# MA_board_1.net
KiCad netlist of a schematic drawn in EAGLE
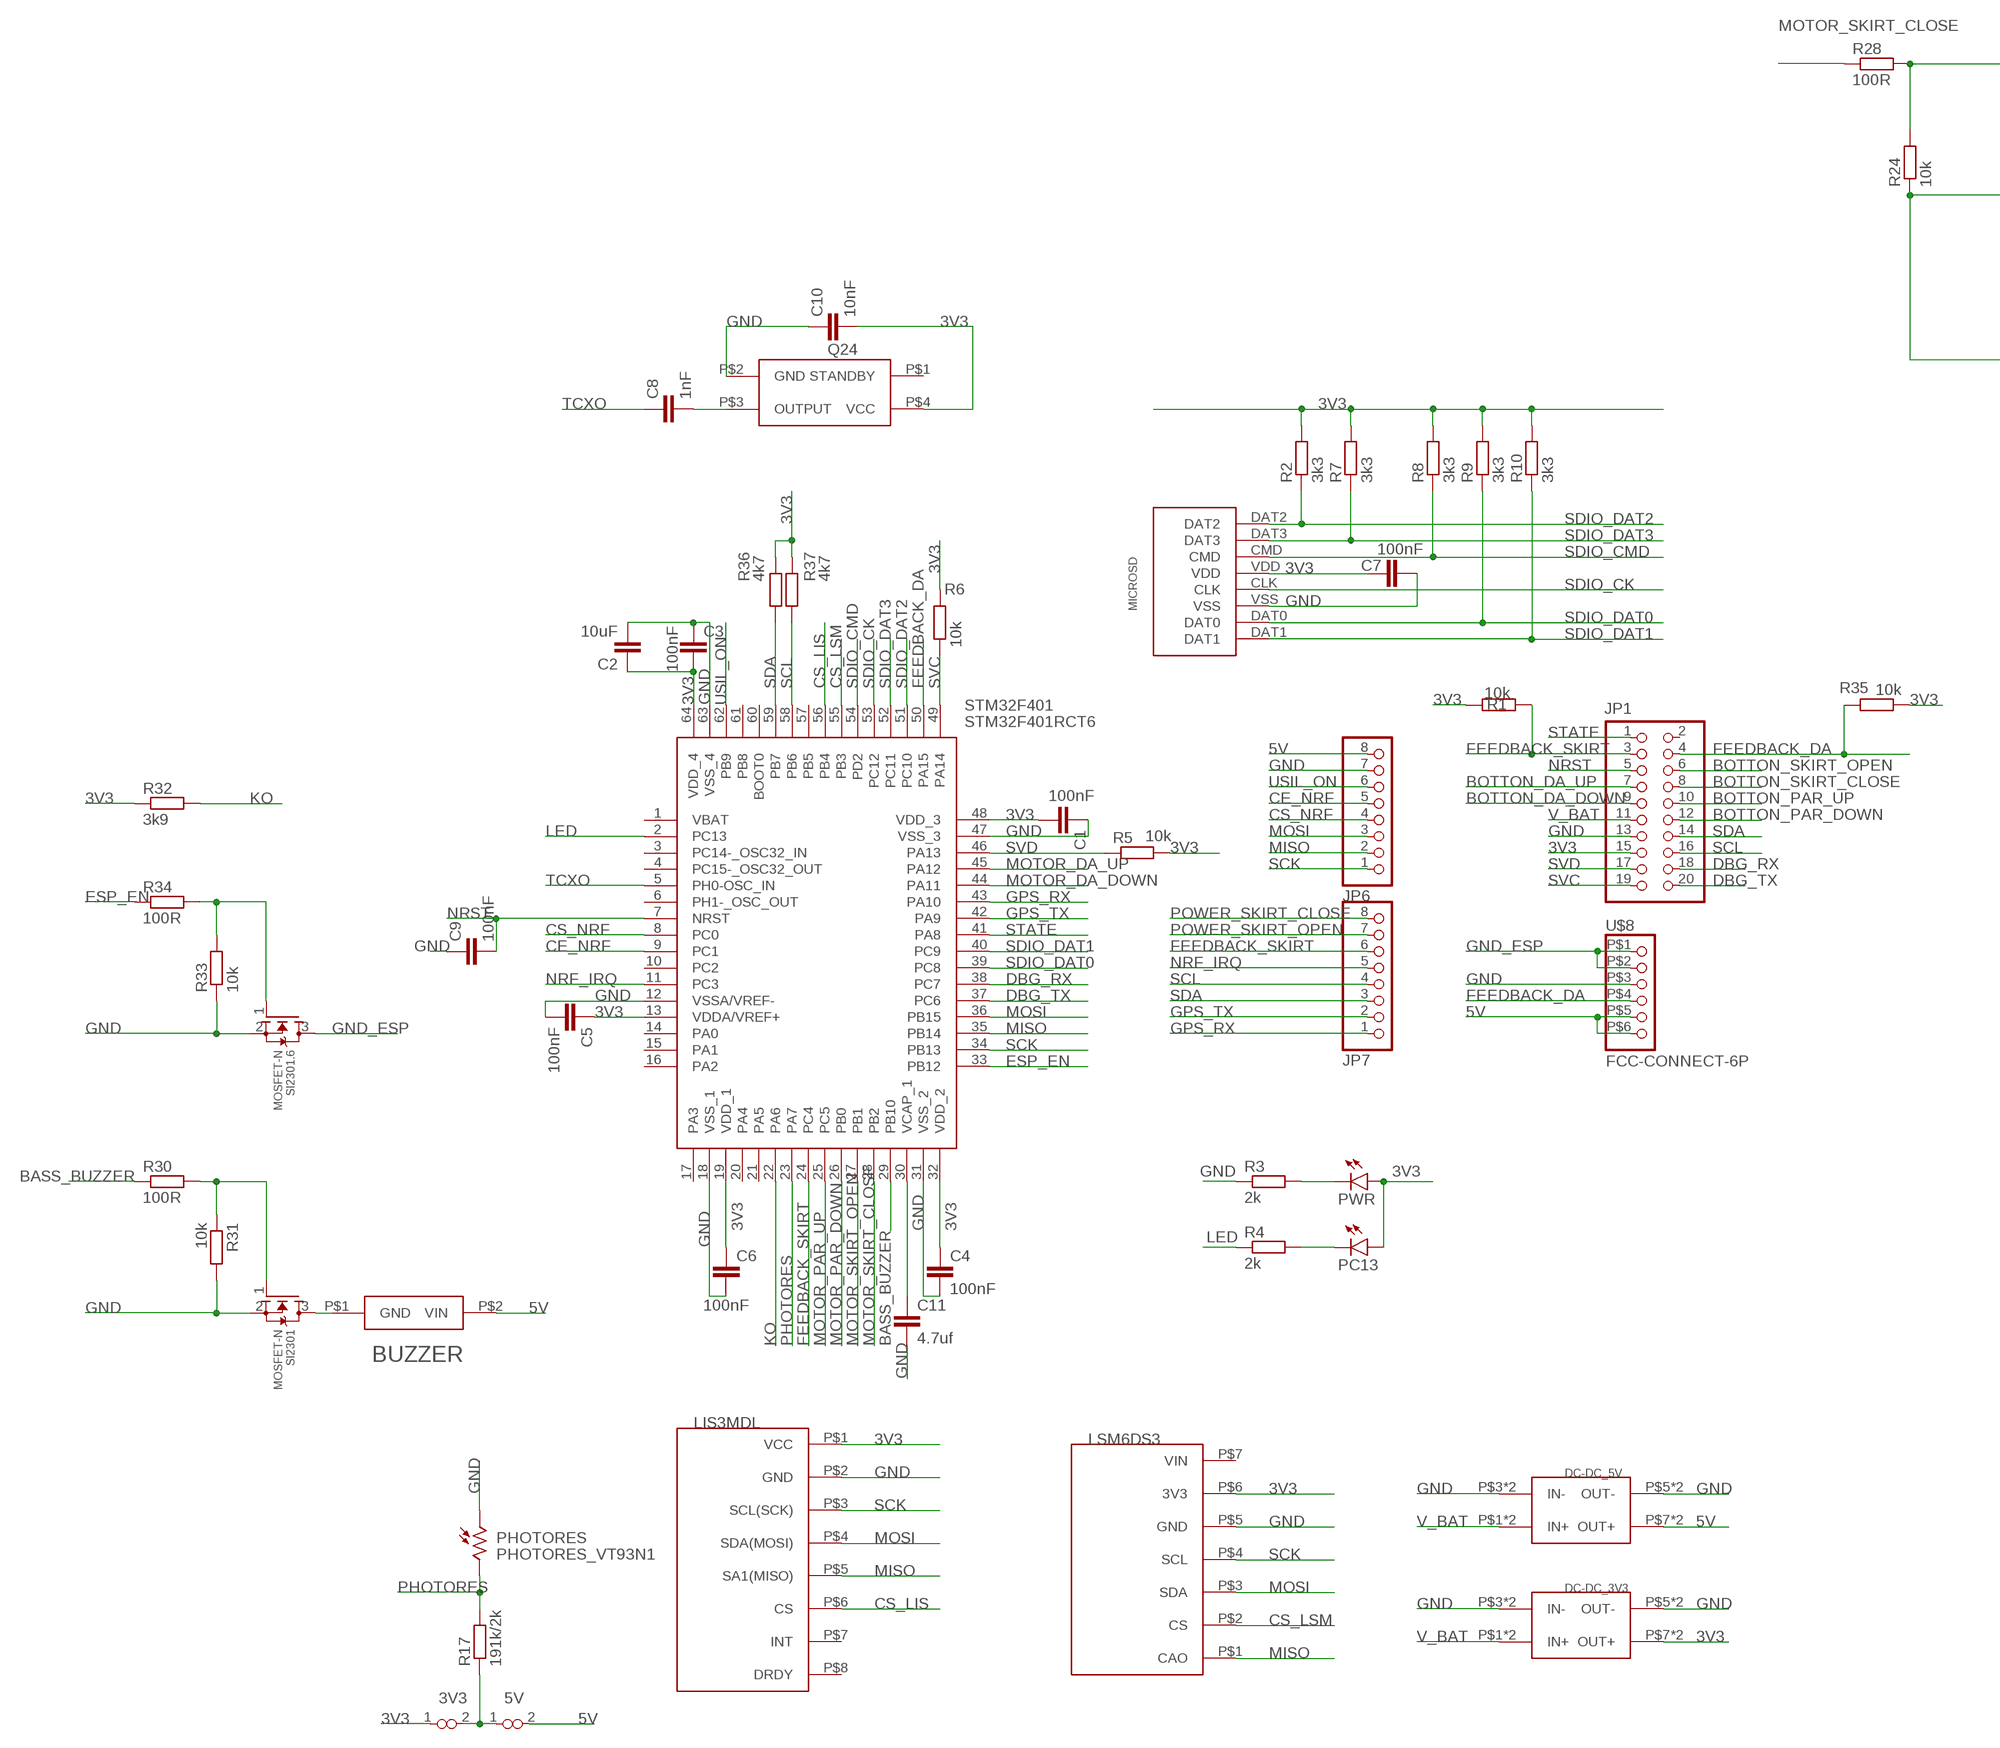
[diagram p0: schematic, sheet 1, part 1 of 2]
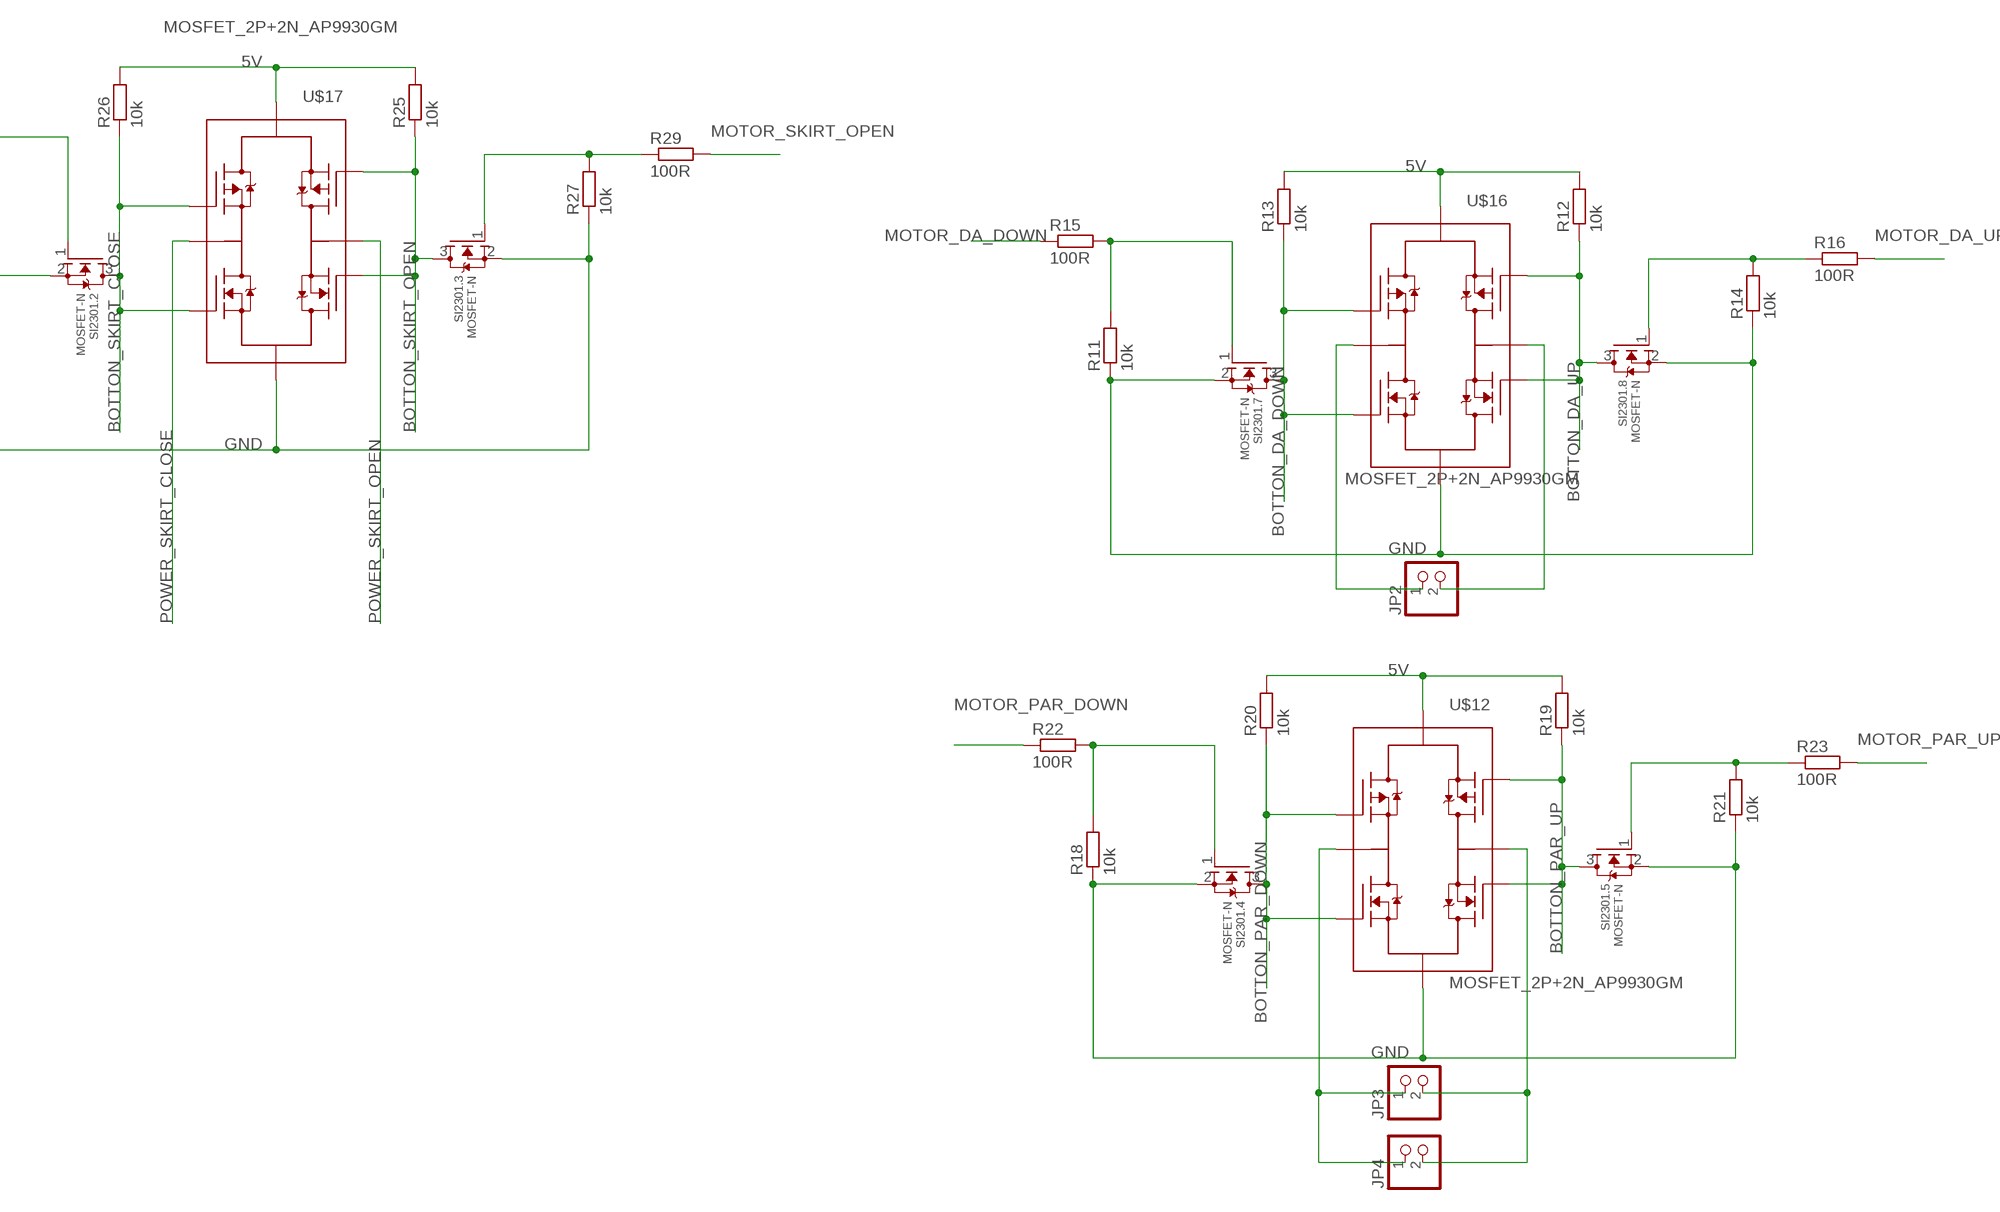
[diagram p1: schematic, sheet 1, part 2 of 2]

(export (version "E")
  (design (tool "Eeschema 10.0.6"))
  (components
    (comp (ref "3V3")
      (value "VIAS-CONNECT")
      (footprint "eagle-import:VIAS-CONNECT")
      (libsource (lib "eagle-import") (part "VIAS-CONNECT"))
    )
    (comp (ref "5V")
      (value "VIAS-CONNECT")
      (footprint "eagle-import:VIAS-CONNECT")
      (libsource (lib "eagle-import") (part "VIAS-CONNECT"))
    )
    (comp (ref "BUZZER")
      (value "BUZZERS8R6")
      (footprint "eagle-import:BUZZER-S8R12")
      (libsource (lib "eagle-import") (part "BUZZERS8R6"))
    )
    (comp (ref "C1")
      (value "100nF")
      (footprint "eagle-import:C0603")
      (libsource (lib "eagle-import") (part "C-EUC0603"))
    )
    (comp (ref "C2")
      (value "10uF")
      (footprint "eagle-import:C1206")
      (libsource (lib "eagle-import") (part "C-EUC1206"))
    )
    (comp (ref "C3")
      (value "100nF")
      (footprint "eagle-import:C0603")
      (libsource (lib "eagle-import") (part "C-EUC0603"))
    )
    (comp (ref "C4")
      (value "100nF")
      (footprint "eagle-import:C0603")
      (libsource (lib "eagle-import") (part "C-EUC0603"))
    )
    (comp (ref "C5")
      (value "100nF")
      (footprint "eagle-import:C0603")
      (libsource (lib "eagle-import") (part "C-EUC0603"))
    )
    (comp (ref "C6")
      (value "100nF")
      (footprint "eagle-import:C0603")
      (libsource (lib "eagle-import") (part "C-EUC0603"))
    )
    (comp (ref "C7")
      (value "100nF")
      (footprint "eagle-import:C0603")
      (libsource (lib "eagle-import") (part "C-EUC0603"))
    )
    (comp (ref "C8")
      (value "1nF")
      (footprint "eagle-import:C0603")
      (libsource (lib "eagle-import") (part "C-EUC0603"))
    )
    (comp (ref "C9")
      (value "100nF")
      (footprint "eagle-import:C0603")
      (libsource (lib "eagle-import") (part "C-EUC0603"))
    )
    (comp (ref "C10")
      (value "10nF")
      (footprint "eagle-import:C0603")
      (libsource (lib "eagle-import") (part "C-EUC0603"))
    )
    (comp (ref "C11")
      (value "4.7uf")
      (footprint "eagle-import:C0603")
      (libsource (lib "eagle-import") (part "C-EUC0603"))
    )
    (comp (ref "DC-DC_3V3")
      (value "MP1584-B")
      (footprint "eagle-import:MP1584-B")
      (libsource (lib "eagle-import") (part "MP1584-B"))
    )
    (comp (ref "DC-DC_5V")
      (value "MP1584-B")
      (footprint "eagle-import:MP1584-B")
      (libsource (lib "eagle-import") (part "MP1584-B"))
    )
    (comp (ref "JP1")
      (value "PINHD-2X10/90")
      (footprint "eagle-import:2X10_90")
      (libsource (lib "eagle-import") (part "PINHD-2X10/90"))
    )
    (comp (ref "JP2")
      (value "PINHD-1X2")
      (footprint "eagle-import:1X02")
      (libsource (lib "eagle-import") (part "PINHD-1X2"))
    )
    (comp (ref "JP3")
      (value "PINHD-1X2")
      (footprint "eagle-import:1X02")
      (libsource (lib "eagle-import") (part "PINHD-1X2"))
    )
    (comp (ref "JP4")
      (value "PINHD-1X2")
      (footprint "eagle-import:1X02")
      (libsource (lib "eagle-import") (part "PINHD-1X2"))
    )
    (comp (ref "JP6")
      (value "PINHD-1X8")
      (footprint "eagle-import:1X08")
      (libsource (lib "eagle-import") (part "PINHD-1X8"))
    )
    (comp (ref "JP7")
      (value "PINHD-1X8")
      (footprint "eagle-import:1X08")
      (libsource (lib "eagle-import") (part "PINHD-1X8"))
    )
    (comp (ref "LIS3MDL")
      (value "LIS3MDL-CJMCUБез_отв._зеркальный")
      (footprint "eagle-import:LIS3MDL-CGMSU-NB2023")
      (libsource (lib "eagle-import") (part "LIS3MDL-CJMCUБез_отв._зеркальный"))
    )
    (comp (ref "LSM6DS3")
      (value "LSM6DS3-GY-NB2023")
      (footprint "eagle-import:LSM6DS3-GY-NB2023")
      (libsource (lib "eagle-import") (part "LSM6DS3-GY-NB2023"))
    )
    (comp (ref "MICROSD")
      (value "SD")
      (footprint "eagle-import:SD")
      (libsource (lib "eagle-import") (part "SD"))
    )
    (comp (ref "PC13")
      (value "LEDCHIPLED_0603")
      (footprint "eagle-import:CHIPLED_0603")
      (libsource (lib "eagle-import") (part "LEDCHIPLED_0603"))
    )
    (comp (ref "PHOTORES")
      (value "PHOTORES_VT93N1")
      (footprint "eagle-import:PHOTORES_VT93N1_SMD")
      (libsource (lib "eagle-import") (part "PHOTORES_VT93N1"))
    )
    (comp (ref "PWR")
      (value "LEDCHIPLED_0603")
      (footprint "eagle-import:CHIPLED_0603")
      (libsource (lib "eagle-import") (part "LEDCHIPLED_0603"))
    )
    (comp (ref "Q24")
      (value "Q24")
      (footprint "eagle-import:Q24")
      (libsource (lib "eagle-import") (part "Q24"))
    )
    (comp (ref "R1")
      (value "10k")
      (footprint "eagle-import:R0603")
      (libsource (lib "eagle-import") (part "R-EU_R0603"))
    )
    (comp (ref "R2")
      (value "3k3")
      (footprint "eagle-import:R0603")
      (libsource (lib "eagle-import") (part "R-EU_R0603"))
    )
    (comp (ref "R3")
      (value "2k")
      (footprint "eagle-import:R0603")
      (libsource (lib "eagle-import") (part "R-EU_R0603"))
    )
    (comp (ref "R4")
      (value "2k")
      (footprint "eagle-import:R0603")
      (libsource (lib "eagle-import") (part "R-EU_R0603"))
    )
    (comp (ref "R5")
      (value "10k")
      (footprint "eagle-import:R0603")
      (libsource (lib "eagle-import") (part "R-EU_R0603"))
    )
    (comp (ref "R6")
      (value "10k")
      (footprint "eagle-import:R0603")
      (libsource (lib "eagle-import") (part "R-EU_R0603"))
    )
    (comp (ref "R7")
      (value "3k3")
      (footprint "eagle-import:R0603")
      (libsource (lib "eagle-import") (part "R-EU_R0603"))
    )
    (comp (ref "R8")
      (value "3k3")
      (footprint "eagle-import:R0603")
      (libsource (lib "eagle-import") (part "R-EU_R0603"))
    )
    (comp (ref "R9")
      (value "3k3")
      (footprint "eagle-import:R0603")
      (libsource (lib "eagle-import") (part "R-EU_R0603"))
    )
    (comp (ref "R10")
      (value "3k3")
      (footprint "eagle-import:R0603")
      (libsource (lib "eagle-import") (part "R-EU_R0603"))
    )
    (comp (ref "R11")
      (value "10k")
      (footprint "eagle-import:R0603")
      (libsource (lib "eagle-import") (part "R-EU_R0603"))
    )
    (comp (ref "R12")
      (value "10k")
      (footprint "eagle-import:R0603")
      (libsource (lib "eagle-import") (part "R-EU_R0603"))
    )
    (comp (ref "R13")
      (value "10k")
      (footprint "eagle-import:R0603")
      (libsource (lib "eagle-import") (part "R-EU_R0603"))
    )
    (comp (ref "R14")
      (value "10k")
      (footprint "eagle-import:R0603")
      (libsource (lib "eagle-import") (part "R-EU_R0603"))
    )
    (comp (ref "R15")
      (value "100R")
      (footprint "eagle-import:R0603")
      (libsource (lib "eagle-import") (part "R-EU_R0603"))
    )
    (comp (ref "R16")
      (value "100R")
      (footprint "eagle-import:R0603")
      (libsource (lib "eagle-import") (part "R-EU_R0603"))
    )
    (comp (ref "R17")
      (value "191k/2k")
      (footprint "eagle-import:R0603")
      (libsource (lib "eagle-import") (part "R-EU_R0603"))
    )
    (comp (ref "R18")
      (value "10k")
      (footprint "eagle-import:R0603")
      (libsource (lib "eagle-import") (part "R-EU_R0603"))
    )
    (comp (ref "R19")
      (value "10k")
      (footprint "eagle-import:R0603")
      (libsource (lib "eagle-import") (part "R-EU_R0603"))
    )
    (comp (ref "R20")
      (value "10k")
      (footprint "eagle-import:R0603")
      (libsource (lib "eagle-import") (part "R-EU_R0603"))
    )
    (comp (ref "R21")
      (value "10k")
      (footprint "eagle-import:R0603")
      (libsource (lib "eagle-import") (part "R-EU_R0603"))
    )
    (comp (ref "R22")
      (value "100R")
      (footprint "eagle-import:R0603")
      (libsource (lib "eagle-import") (part "R-EU_R0603"))
    )
    (comp (ref "R23")
      (value "100R")
      (footprint "eagle-import:R0603")
      (libsource (lib "eagle-import") (part "R-EU_R0603"))
    )
    (comp (ref "R24")
      (value "10k")
      (footprint "eagle-import:R0603")
      (libsource (lib "eagle-import") (part "R-EU_R0603"))
    )
    (comp (ref "R25")
      (value "10k")
      (footprint "eagle-import:R0603")
      (libsource (lib "eagle-import") (part "R-EU_R0603"))
    )
    (comp (ref "R26")
      (value "10k")
      (footprint "eagle-import:R0603")
      (libsource (lib "eagle-import") (part "R-EU_R0603"))
    )
    (comp (ref "R27")
      (value "10k")
      (footprint "eagle-import:R0603")
      (libsource (lib "eagle-import") (part "R-EU_R0603"))
    )
    (comp (ref "R28")
      (value "100R")
      (footprint "eagle-import:R0603")
      (libsource (lib "eagle-import") (part "R-EU_R0603"))
    )
    (comp (ref "R29")
      (value "100R")
      (footprint "eagle-import:R0603")
      (libsource (lib "eagle-import") (part "R-EU_R0603"))
    )
    (comp (ref "R30")
      (value "100R")
      (footprint "eagle-import:R0603")
      (libsource (lib "eagle-import") (part "R-EU_R0603"))
    )
    (comp (ref "R31")
      (value "10k")
      (footprint "eagle-import:R0603")
      (libsource (lib "eagle-import") (part "R-EU_R0603"))
    )
    (comp (ref "R32")
      (value "3k9")
      (footprint "eagle-import:R0603")
      (libsource (lib "eagle-import") (part "R-EU_R0603"))
    )
    (comp (ref "R33")
      (value "10k")
      (footprint "eagle-import:R0603")
      (libsource (lib "eagle-import") (part "R-EU_R0603"))
    )
    (comp (ref "R34")
      (value "100R")
      (footprint "eagle-import:R0603")
      (libsource (lib "eagle-import") (part "R-EU_R0603"))
    )
    (comp (ref "R35")
      (value "10k")
      (footprint "eagle-import:R0603")
      (libsource (lib "eagle-import") (part "R-EU_R0603"))
    )
    (comp (ref "R36")
      (value "4k7")
      (footprint "eagle-import:R0603")
      (libsource (lib "eagle-import") (part "R-EU_R0603"))
    )
    (comp (ref "R37")
      (value "4k7")
      (footprint "eagle-import:R0603")
      (libsource (lib "eagle-import") (part "R-EU_R0603"))
    )
    (comp (ref "SI2301")
      (value "MOSFET-N")
      (footprint "eagle-import:SOT23-3")
      (libsource (lib "eagle-import") (part "MOSFET-N"))
    )
    (comp (ref "SI2301.2")
      (value "MOSFET-N")
      (footprint "eagle-import:SOT23-3")
      (libsource (lib "eagle-import") (part "MOSFET-N"))
    )
    (comp (ref "SI2301.3")
      (value "MOSFET-N")
      (footprint "eagle-import:SOT23-3")
      (libsource (lib "eagle-import") (part "MOSFET-N"))
    )
    (comp (ref "SI2301.4")
      (value "MOSFET-N")
      (footprint "eagle-import:SOT23-3")
      (libsource (lib "eagle-import") (part "MOSFET-N"))
    )
    (comp (ref "SI2301.5")
      (value "MOSFET-N")
      (footprint "eagle-import:SOT23-3")
      (libsource (lib "eagle-import") (part "MOSFET-N"))
    )
    (comp (ref "SI2301.6")
      (value "MOSFET-N")
      (footprint "eagle-import:SOT23-3")
      (libsource (lib "eagle-import") (part "MOSFET-N"))
    )
    (comp (ref "SI2301.7")
      (value "MOSFET-N")
      (footprint "eagle-import:SOT23-3")
      (libsource (lib "eagle-import") (part "MOSFET-N"))
    )
    (comp (ref "SI2301.8")
      (value "MOSFET-N")
      (footprint "eagle-import:SOT23-3")
      (libsource (lib "eagle-import") (part "MOSFET-N"))
    )
    (comp (ref "STM32F401")
      (value "STM32F401RCT6")
      (footprint "eagle-import:QFP50P1200X1200X160-64N")
      (fields (field (name "MOUSER_PART_NUMBER") "511-STM32F401RCT6"))
      (libsource (lib "eagle-import") (part "STM32F401RCT6"))
    )
    (comp (ref "U$8")
      (value "FCC-CONNECT-6P")
      (footprint "eagle-import:FFC-CONNECT-6P-SMD")
      (libsource (lib "eagle-import") (part "FCC-CONNECT-6P"))
    )
    (comp (ref "U$12")
      (value "MOSFET_2P+2N_AP9930GM")
      (footprint "eagle-import:SO8")
      (libsource (lib "eagle-import") (part "MOSFET_2P+2N_AP9930GM"))
    )
    (comp (ref "U$16")
      (value "MOSFET_2P+2N_AP9930GM")
      (footprint "eagle-import:SO8")
      (libsource (lib "eagle-import") (part "MOSFET_2P+2N_AP9930GM"))
    )
    (comp (ref "U$17")
      (value "MOSFET_2P+2N_AP9930GM")
      (footprint "eagle-import:SO8")
      (libsource (lib "eagle-import") (part "MOSFET_2P+2N_AP9930GM"))
    )
  )
  (nets
    (net (code "1") (name "/3V3") (class "Default")
      (node (ref "3V3") (pin "1") (pinfunction "1_1") (pintype "passive"))
      (node (ref "C1") (pin "2") (pinfunction "2_2") (pintype "passive"))
      (node (ref "C10") (pin "2") (pinfunction "2_2") (pintype "passive"))
      (node (ref "C2") (pin "1") (pinfunction "1_1") (pintype "passive"))
      (node (ref "C3") (pin "2") (pinfunction "2_2") (pintype "passive"))
      (node (ref "C4") (pin "1") (pinfunction "1_1") (pintype "passive"))
      (node (ref "C5") (pin "1") (pinfunction "1_1") (pintype "passive"))
      (node (ref "C6") (pin "1") (pinfunction "1_1") (pintype "passive"))
      (node (ref "C7") (pin "2") (pinfunction "2_2") (pintype "passive"))
      (node (ref "DC-DC_3V3") (pin "P$7") (pinfunction "OUT+_P$7") (pintype "bidirectional"))
      (node (ref "DC-DC_3V3") (pin "P$8") (pinfunction "OUT+_P$8") (pintype "bidirectional"))
      (node (ref "JP1") (pin "15") (pinfunction "15_15") (pintype "passive"))
      (node (ref "LIS3MDL") (pin "P$1") (pinfunction "VCC_P$1") (pintype "bidirectional"))
      (node (ref "LSM6DS3") (pin "P$6") (pinfunction "3V3_P$6") (pintype "bidirectional"))
      (node (ref "MICROSD") (pin "VDD") (pinfunction "VDD_VDD") (pintype "bidirectional"))
      (node (ref "PC13") (pin "A") (pinfunction "A_A") (pintype "passive"))
      (node (ref "PWR") (pin "A") (pinfunction "A_A") (pintype "passive"))
      (node (ref "Q24") (pin "P$4") (pinfunction "VCC_P$4") (pintype "bidirectional"))
      (node (ref "R1") (pin "2") (pinfunction "2_2") (pintype "passive"))
      (node (ref "R10") (pin "2") (pinfunction "2_2") (pintype "passive"))
      (node (ref "R2") (pin "2") (pinfunction "2_2") (pintype "passive"))
      (node (ref "R32") (pin "1") (pinfunction "1_1") (pintype "passive"))
      (node (ref "R35") (pin "1") (pinfunction "1_1") (pintype "passive"))
      (node (ref "R36") (pin "2") (pinfunction "2_2") (pintype "passive"))
      (node (ref "R37") (pin "2") (pinfunction "2_2") (pintype "passive"))
      (node (ref "R5") (pin "2") (pinfunction "2_2") (pintype "passive"))
      (node (ref "R6") (pin "2") (pinfunction "2_2") (pintype "passive"))
      (node (ref "R7") (pin "2") (pinfunction "2_2") (pintype "passive"))
      (node (ref "R8") (pin "2") (pinfunction "2_2") (pintype "passive"))
      (node (ref "R9") (pin "2") (pinfunction "2_2") (pintype "passive"))
      (node (ref "STM32F401") (pin "13") (pinfunction "VDDA/VREF+_13") (pintype "bidirectional"))
      (node (ref "STM32F401") (pin "19") (pinfunction "VDD_1_19") (pintype "bidirectional"))
      (node (ref "STM32F401") (pin "32") (pinfunction "VDD_2_32") (pintype "bidirectional"))
      (node (ref "STM32F401") (pin "48") (pinfunction "VDD_3_48") (pintype "bidirectional"))
      (node (ref "STM32F401") (pin "64") (pinfunction "VDD_4_64") (pintype "bidirectional"))
    )
    (net (code "2") (name "/5V") (class "Default")
      (node (ref "5V") (pin "2") (pinfunction "2_2") (pintype "passive"))
      (node (ref "BUZZER") (pin "P$2") (pinfunction "VIN_P$2") (pintype "bidirectional"))
      (node (ref "DC-DC_5V") (pin "P$7") (pinfunction "OUT+_P$7") (pintype "bidirectional"))
      (node (ref "DC-DC_5V") (pin "P$8") (pinfunction "OUT+_P$8") (pintype "bidirectional"))
      (node (ref "JP6") (pin "8") (pinfunction "8_8") (pintype "passive"))
      (node (ref "R12") (pin "2") (pinfunction "2_2") (pintype "passive"))
      (node (ref "R13") (pin "2") (pinfunction "2_2") (pintype "passive"))
      (node (ref "R19") (pin "2") (pinfunction "2_2") (pintype "passive"))
      (node (ref "R20") (pin "2") (pinfunction "2_2") (pintype "passive"))
      (node (ref "R25") (pin "2") (pinfunction "2_2") (pintype "passive"))
      (node (ref "R26") (pin "2") (pinfunction "2_2") (pintype "passive"))
      (node (ref "U$12") (pin "7") (pinfunction "P1P2S_7") (pintype "passive"))
      (node (ref "U$16") (pin "7") (pinfunction "P1P2S_7") (pintype "passive"))
      (node (ref "U$17") (pin "7") (pinfunction "P1P2S_7") (pintype "passive"))
      (node (ref "U$8") (pin "P$5") (pinfunction "5_P$5") (pintype "passive"))
      (node (ref "U$8") (pin "P$6") (pinfunction "6_P$6") (pintype "passive"))
    )
    (net (code "3") (name "/BASS_BUZZER") (class "Default")
      (node (ref "R30") (pin "1") (pinfunction "1_1") (pintype "passive"))
      (node (ref "STM32F401") (pin "29") (pinfunction "PB10_29") (pintype "bidirectional"))
    )
    (net (code "4") (name "/BOTTON_DA_DOWN") (class "Default")
      (node (ref "JP1") (pin "9") (pinfunction "9_9") (pintype "passive"))
      (node (ref "R13") (pin "1") (pinfunction "1_1") (pintype "passive"))
      (node (ref "SI2301.7") (pin "3") (pinfunction "D_3") (pintype "bidirectional"))
      (node (ref "U$16") (pin "1") (pinfunction "N1G_1") (pintype "passive"))
      (node (ref "U$16") (pin "8") (pinfunction "P1G_8") (pintype "passive"))
    )
    (net (code "5") (name "/BOTTON_DA_UP") (class "Default")
      (node (ref "JP1") (pin "7") (pinfunction "7_7") (pintype "passive"))
      (node (ref "R12") (pin "1") (pinfunction "1_1") (pintype "passive"))
      (node (ref "SI2301.8") (pin "3") (pinfunction "D_3") (pintype "bidirectional"))
      (node (ref "U$16") (pin "4") (pinfunction "N2G_4") (pintype "passive"))
      (node (ref "U$16") (pin "5") (pinfunction "P2G_5") (pintype "passive"))
    )
    (net (code "6") (name "/BOTTON_PAR_DOWN") (class "Default")
      (node (ref "JP1") (pin "12") (pinfunction "12_12") (pintype "passive"))
      (node (ref "R20") (pin "1") (pinfunction "1_1") (pintype "passive"))
      (node (ref "SI2301.4") (pin "3") (pinfunction "D_3") (pintype "bidirectional"))
      (node (ref "U$12") (pin "1") (pinfunction "N1G_1") (pintype "passive"))
      (node (ref "U$12") (pin "8") (pinfunction "P1G_8") (pintype "passive"))
    )
    (net (code "7") (name "/BOTTON_PAR_UP") (class "Default")
      (node (ref "JP1") (pin "10") (pinfunction "10_10") (pintype "passive"))
      (node (ref "R19") (pin "1") (pinfunction "1_1") (pintype "passive"))
      (node (ref "SI2301.5") (pin "3") (pinfunction "D_3") (pintype "bidirectional"))
      (node (ref "U$12") (pin "4") (pinfunction "N2G_4") (pintype "passive"))
      (node (ref "U$12") (pin "5") (pinfunction "P2G_5") (pintype "passive"))
    )
    (net (code "8") (name "/BOTTON_SKIRT_CLOSE") (class "Default")
      (node (ref "JP1") (pin "8") (pinfunction "8_8") (pintype "passive"))
      (node (ref "R26") (pin "1") (pinfunction "1_1") (pintype "passive"))
      (node (ref "SI2301.2") (pin "3") (pinfunction "D_3") (pintype "bidirectional"))
      (node (ref "U$17") (pin "1") (pinfunction "N1G_1") (pintype "passive"))
      (node (ref "U$17") (pin "8") (pinfunction "P1G_8") (pintype "passive"))
    )
    (net (code "9") (name "/BOTTON_SKIRT_OPEN") (class "Default")
      (node (ref "JP1") (pin "6") (pinfunction "6_6") (pintype "passive"))
      (node (ref "R25") (pin "1") (pinfunction "1_1") (pintype "passive"))
      (node (ref "SI2301.3") (pin "3") (pinfunction "D_3") (pintype "bidirectional"))
      (node (ref "U$17") (pin "4") (pinfunction "N2G_4") (pintype "passive"))
      (node (ref "U$17") (pin "5") (pinfunction "P2G_5") (pintype "passive"))
    )
    (net (code "10") (name "/CE_NRF") (class "Default")
      (node (ref "JP6") (pin "5") (pinfunction "5_5") (pintype "passive"))
      (node (ref "STM32F401") (pin "9") (pinfunction "PC1_9") (pintype "bidirectional"))
    )
    (net (code "11") (name "/CS_LIS") (class "Default")
      (node (ref "LIS3MDL") (pin "P$6") (pinfunction "CS_P$6") (pintype "bidirectional"))
      (node (ref "STM32F401") (pin "56") (pinfunction "PB4_56") (pintype "bidirectional"))
    )
    (net (code "12") (name "/CS_LSM") (class "Default")
      (node (ref "LSM6DS3") (pin "P$2") (pinfunction "CS_P$2") (pintype "bidirectional"))
      (node (ref "STM32F401") (pin "55") (pinfunction "PB3_55") (pintype "bidirectional"))
    )
    (net (code "13") (name "/CS_NRF") (class "Default")
      (node (ref "JP6") (pin "4") (pinfunction "4_4") (pintype "passive"))
      (node (ref "STM32F401") (pin "8") (pinfunction "PC0_8") (pintype "bidirectional"))
    )
    (net (code "14") (name "/DBG_RX") (class "Default")
      (node (ref "JP1") (pin "18") (pinfunction "18_18") (pintype "passive"))
      (node (ref "STM32F401") (pin "38") (pinfunction "PC7_38") (pintype "bidirectional"))
    )
    (net (code "15") (name "/DBG_TX") (class "Default")
      (node (ref "JP1") (pin "20") (pinfunction "20_20") (pintype "passive"))
      (node (ref "STM32F401") (pin "37") (pinfunction "PC6_37") (pintype "bidirectional"))
    )
    (net (code "16") (name "/ESP_EN") (class "Default")
      (node (ref "R34") (pin "1") (pinfunction "1_1") (pintype "passive"))
      (node (ref "STM32F401") (pin "33") (pinfunction "PB12_33") (pintype "bidirectional"))
    )
    (net (code "17") (name "/FEEDBACK_DA") (class "Default")
      (node (ref "JP1") (pin "4") (pinfunction "4_4") (pintype "passive"))
      (node (ref "R35") (pin "2") (pinfunction "2_2") (pintype "passive"))
      (node (ref "STM32F401") (pin "50") (pinfunction "PA15_50") (pintype "bidirectional"))
      (node (ref "U$8") (pin "P$4") (pinfunction "4_P$4") (pintype "passive"))
    )
    (net (code "18") (name "/FEEDBACK_SKIRT") (class "Default")
      (node (ref "JP1") (pin "3") (pinfunction "3_3") (pintype "passive"))
      (node (ref "JP7") (pin "6") (pinfunction "6_6") (pintype "passive"))
      (node (ref "R1") (pin "1") (pinfunction "1_1") (pintype "passive"))
      (node (ref "STM32F401") (pin "24") (pinfunction "PC4_24") (pintype "bidirectional"))
    )
    (net (code "19") (name "/GND") (class "Default")
      (node (ref "C1") (pin "1") (pinfunction "1_1") (pintype "passive"))
      (node (ref "C10") (pin "1") (pinfunction "1_1") (pintype "passive"))
      (node (ref "C11") (pin "2") (pinfunction "2_2") (pintype "passive"))
      (node (ref "C2") (pin "2") (pinfunction "2_2") (pintype "passive"))
      (node (ref "C3") (pin "1") (pinfunction "1_1") (pintype "passive"))
      (node (ref "C4") (pin "2") (pinfunction "2_2") (pintype "passive"))
      (node (ref "C5") (pin "2") (pinfunction "2_2") (pintype "passive"))
      (node (ref "C6") (pin "2") (pinfunction "2_2") (pintype "passive"))
      (node (ref "C7") (pin "1") (pinfunction "1_1") (pintype "passive"))
      (node (ref "C9") (pin "1") (pinfunction "1_1") (pintype "passive"))
      (node (ref "DC-DC_3V3") (pin "P$3") (pinfunction "IN-_P$3") (pintype "bidirectional"))
      (node (ref "DC-DC_3V3") (pin "P$4") (pinfunction "IN-_P$4") (pintype "bidirectional"))
      (node (ref "DC-DC_3V3") (pin "P$5") (pinfunction "OUT-_P$5") (pintype "bidirectional"))
      (node (ref "DC-DC_3V3") (pin "P$6") (pinfunction "OUT-_P$6") (pintype "bidirectional"))
      (node (ref "DC-DC_5V") (pin "P$3") (pinfunction "IN-_P$3") (pintype "bidirectional"))
      (node (ref "DC-DC_5V") (pin "P$4") (pinfunction "IN-_P$4") (pintype "bidirectional"))
      (node (ref "DC-DC_5V") (pin "P$5") (pinfunction "OUT-_P$5") (pintype "bidirectional"))
      (node (ref "DC-DC_5V") (pin "P$6") (pinfunction "OUT-_P$6") (pintype "bidirectional"))
      (node (ref "JP1") (pin "13") (pinfunction "13_13") (pintype "passive"))
      (node (ref "JP6") (pin "7") (pinfunction "7_7") (pintype "passive"))
      (node (ref "LIS3MDL") (pin "P$2") (pinfunction "GND_P$2") (pintype "bidirectional"))
      (node (ref "LSM6DS3") (pin "P$5") (pinfunction "GND_P$5") (pintype "bidirectional"))
      (node (ref "MICROSD") (pin "VSS") (pinfunction "VSS_VSS") (pintype "bidirectional"))
      (node (ref "PHOTORES") (pin "P$1") (pinfunction "1_P$1") (pintype "passive"))
      (node (ref "Q24") (pin "P$2") (pinfunction "GND_P$2") (pintype "bidirectional"))
      (node (ref "R11") (pin "1") (pinfunction "1_1") (pintype "passive"))
      (node (ref "R14") (pin "1") (pinfunction "1_1") (pintype "passive"))
      (node (ref "R18") (pin "1") (pinfunction "1_1") (pintype "passive"))
      (node (ref "R21") (pin "1") (pinfunction "1_1") (pintype "passive"))
      (node (ref "R24") (pin "1") (pinfunction "1_1") (pintype "passive"))
      (node (ref "R27") (pin "1") (pinfunction "1_1") (pintype "passive"))
      (node (ref "R3") (pin "1") (pinfunction "1_1") (pintype "passive"))
      (node (ref "R31") (pin "2") (pinfunction "2_2") (pintype "passive"))
      (node (ref "R33") (pin "1") (pinfunction "1_1") (pintype "passive"))
      (node (ref "SI2301") (pin "2") (pinfunction "S_2") (pintype "bidirectional"))
      (node (ref "SI2301.2") (pin "2") (pinfunction "S_2") (pintype "bidirectional"))
      (node (ref "SI2301.3") (pin "2") (pinfunction "S_2") (pintype "bidirectional"))
      (node (ref "SI2301.4") (pin "2") (pinfunction "S_2") (pintype "bidirectional"))
      (node (ref "SI2301.5") (pin "2") (pinfunction "S_2") (pintype "bidirectional"))
      (node (ref "SI2301.6") (pin "2") (pinfunction "S_2") (pintype "bidirectional"))
      (node (ref "SI2301.7") (pin "2") (pinfunction "S_2") (pintype "bidirectional"))
      (node (ref "SI2301.8") (pin "2") (pinfunction "S_2") (pintype "bidirectional"))
      (node (ref "STM32F401") (pin "12") (pinfunction "VSSA/VREF-_12") (pintype "bidirectional"))
      (node (ref "STM32F401") (pin "18") (pinfunction "VSS_1_18") (pintype "bidirectional"))
      (node (ref "STM32F401") (pin "31") (pinfunction "VSS_2_31") (pintype "bidirectional"))
      (node (ref "STM32F401") (pin "47") (pinfunction "VSS_3_47") (pintype "bidirectional"))
      (node (ref "STM32F401") (pin "63") (pinfunction "VSS_4_63") (pintype "bidirectional"))
      (node (ref "U$12") (pin "3") (pinfunction "N1N2S_3") (pintype "passive"))
      (node (ref "U$16") (pin "3") (pinfunction "N1N2S_3") (pintype "passive"))
      (node (ref "U$17") (pin "3") (pinfunction "N1N2S_3") (pintype "passive"))
      (node (ref "U$8") (pin "P$3") (pinfunction "3_P$3") (pintype "passive"))
    )
    (net (code "20") (name "/GND_ESP") (class "Default")
      (node (ref "SI2301.6") (pin "3") (pinfunction "D_3") (pintype "bidirectional"))
      (node (ref "U$8") (pin "P$1") (pinfunction "1_P$1") (pintype "passive"))
      (node (ref "U$8") (pin "P$2") (pinfunction "2_P$2") (pintype "passive"))
    )
    (net (code "21") (name "/GPS_RX") (class "Default")
      (node (ref "JP7") (pin "1") (pinfunction "1_1") (pintype "passive"))
      (node (ref "STM32F401") (pin "43") (pinfunction "PA10_43") (pintype "bidirectional"))
    )
    (net (code "22") (name "/GPS_TX") (class "Default")
      (node (ref "JP7") (pin "2") (pinfunction "2_2") (pintype "passive"))
      (node (ref "STM32F401") (pin "42") (pinfunction "PA9_42") (pintype "bidirectional"))
    )
    (net (code "23") (name "/KO") (class "Default")
      (node (ref "R32") (pin "2") (pinfunction "2_2") (pintype "passive"))
      (node (ref "STM32F401") (pin "22") (pinfunction "PA6_22") (pintype "bidirectional"))
    )
    (net (code "24") (name "/LED") (class "Default")
      (node (ref "R4") (pin "1") (pinfunction "1_1") (pintype "passive"))
      (node (ref "STM32F401") (pin "2") (pinfunction "PC13_2") (pintype "bidirectional"))
    )
    (net (code "25") (name "/MISO") (class "Default")
      (node (ref "JP6") (pin "2") (pinfunction "2_2") (pintype "passive"))
      (node (ref "LIS3MDL") (pin "P$5") (pinfunction "SA1(MISO)_P$5") (pintype "bidirectional"))
      (node (ref "LSM6DS3") (pin "P$1") (pinfunction "CAO_P$1") (pintype "bidirectional"))
      (node (ref "STM32F401") (pin "35") (pinfunction "PB14_35") (pintype "bidirectional"))
    )
    (net (code "26") (name "/MOSI") (class "Default")
      (node (ref "JP6") (pin "3") (pinfunction "3_3") (pintype "passive"))
      (node (ref "LIS3MDL") (pin "P$4") (pinfunction "SDA(MOSI)_P$4") (pintype "bidirectional"))
      (node (ref "LSM6DS3") (pin "P$3") (pinfunction "SDA_P$3") (pintype "bidirectional"))
      (node (ref "STM32F401") (pin "36") (pinfunction "PB15_36") (pintype "bidirectional"))
    )
    (net (code "27") (name "/MOTOR_DA_DOWN") (class "Default")
      (node (ref "R15") (pin "1") (pinfunction "1_1") (pintype "passive"))
      (node (ref "STM32F401") (pin "44") (pinfunction "PA11_44") (pintype "bidirectional"))
    )
    (net (code "28") (name "/MOTOR_DA_UP") (class "Default")
      (node (ref "R16") (pin "2") (pinfunction "2_2") (pintype "passive"))
      (node (ref "STM32F401") (pin "45") (pinfunction "PA12_45") (pintype "bidirectional"))
    )
    (net (code "29") (name "/MOTOR_PAR_DOWN") (class "Default")
      (node (ref "R22") (pin "1") (pinfunction "1_1") (pintype "passive"))
      (node (ref "STM32F401") (pin "26") (pinfunction "PB0_26") (pintype "bidirectional"))
    )
    (net (code "30") (name "/MOTOR_PAR_UP") (class "Default")
      (node (ref "R23") (pin "2") (pinfunction "2_2") (pintype "passive"))
      (node (ref "STM32F401") (pin "25") (pinfunction "PC5_25") (pintype "bidirectional"))
    )
    (net (code "31") (name "/MOTOR_SKIRT_CLOSE") (class "Default")
      (node (ref "R28") (pin "1") (pinfunction "1_1") (pintype "passive"))
      (node (ref "STM32F401") (pin "28") (pinfunction "PB2_28") (pintype "bidirectional"))
    )
    (net (code "32") (name "/MOTOR_SKIRT_OPEN") (class "Default")
      (node (ref "R29") (pin "2") (pinfunction "2_2") (pintype "passive"))
      (node (ref "STM32F401") (pin "27") (pinfunction "PB1_27") (pintype "bidirectional"))
    )
    (net (code "33") (name "/NRF_IRQ") (class "Default")
      (node (ref "JP7") (pin "5") (pinfunction "5_5") (pintype "passive"))
      (node (ref "STM32F401") (pin "11") (pinfunction "PC3_11") (pintype "bidirectional"))
    )
    (net (code "34") (name "/NRST") (class "Default")
      (node (ref "C9") (pin "2") (pinfunction "2_2") (pintype "passive"))
      (node (ref "JP1") (pin "5") (pinfunction "5_5") (pintype "passive"))
      (node (ref "STM32F401") (pin "7") (pinfunction "NRST_7") (pintype "bidirectional"))
    )
    (net (code "35") (name "/PHOTORES") (class "Default")
      (node (ref "PHOTORES") (pin "P$2") (pinfunction "2_P$2") (pintype "passive"))
      (node (ref "R17") (pin "2") (pinfunction "2_2") (pintype "passive"))
      (node (ref "STM32F401") (pin "23") (pinfunction "PA7_23") (pintype "bidirectional"))
    )
    (net (code "36") (name "/POWER_SKIRT_CLOSE") (class "Default")
      (node (ref "JP7") (pin "8") (pinfunction "8_8") (pintype "passive"))
      (node (ref "U$17") (pin "2") (pinfunction "P1N1D_2") (pintype "passive"))
    )
    (net (code "37") (name "/POWER_SKIRT_OPEN") (class "Default")
      (node (ref "JP7") (pin "7") (pinfunction "7_7") (pintype "passive"))
      (node (ref "U$17") (pin "6") (pinfunction "P2N2D_6") (pintype "passive"))
    )
    (net (code "38") (name "/SCK") (class "Default")
      (node (ref "JP6") (pin "1") (pinfunction "1_1") (pintype "passive"))
      (node (ref "LIS3MDL") (pin "P$3") (pinfunction "SCL(SCK)_P$3") (pintype "bidirectional"))
      (node (ref "LSM6DS3") (pin "P$4") (pinfunction "SCL_P$4") (pintype "bidirectional"))
      (node (ref "STM32F401") (pin "34") (pinfunction "PB13_34") (pintype "bidirectional"))
    )
    (net (code "39") (name "/SCL") (class "Default")
      (node (ref "JP1") (pin "16") (pinfunction "16_16") (pintype "passive"))
      (node (ref "JP7") (pin "4") (pinfunction "4_4") (pintype "passive"))
      (node (ref "R37") (pin "1") (pinfunction "1_1") (pintype "passive"))
      (node (ref "STM32F401") (pin "58") (pinfunction "PB6_58") (pintype "bidirectional"))
    )
    (net (code "40") (name "/SDA") (class "Default")
      (node (ref "JP1") (pin "14") (pinfunction "14_14") (pintype "passive"))
      (node (ref "JP7") (pin "3") (pinfunction "3_3") (pintype "passive"))
      (node (ref "R36") (pin "1") (pinfunction "1_1") (pintype "passive"))
      (node (ref "STM32F401") (pin "59") (pinfunction "PB7_59") (pintype "bidirectional"))
    )
    (net (code "41") (name "/SDIO_CK") (class "Default")
      (node (ref "MICROSD") (pin "CLK") (pinfunction "CLK_CLK") (pintype "bidirectional"))
      (node (ref "STM32F401") (pin "53") (pinfunction "PC12_53") (pintype "bidirectional"))
    )
    (net (code "42") (name "/SDIO_CMD") (class "Default")
      (node (ref "MICROSD") (pin "CMD") (pinfunction "CMD_CMD") (pintype "bidirectional"))
      (node (ref "R8") (pin "1") (pinfunction "1_1") (pintype "passive"))
      (node (ref "STM32F401") (pin "54") (pinfunction "PD2_54") (pintype "bidirectional"))
    )
    (net (code "43") (name "/SDIO_DAT0") (class "Default")
      (node (ref "MICROSD") (pin "DAT0") (pinfunction "DAT0_DAT0") (pintype "bidirectional"))
      (node (ref "R9") (pin "1") (pinfunction "1_1") (pintype "passive"))
      (node (ref "STM32F401") (pin "39") (pinfunction "PC8_39") (pintype "bidirectional"))
    )
    (net (code "44") (name "/SDIO_DAT1") (class "Default")
      (node (ref "MICROSD") (pin "DAT1") (pinfunction "DAT1_DAT1") (pintype "bidirectional"))
      (node (ref "R10") (pin "1") (pinfunction "1_1") (pintype "passive"))
      (node (ref "STM32F401") (pin "40") (pinfunction "PC9_40") (pintype "bidirectional"))
    )
    (net (code "45") (name "/SDIO_DAT2") (class "Default")
      (node (ref "MICROSD") (pin "DAT2") (pinfunction "DAT2_DAT2") (pintype "bidirectional"))
      (node (ref "R2") (pin "1") (pinfunction "1_1") (pintype "passive"))
      (node (ref "STM32F401") (pin "51") (pinfunction "PC10_51") (pintype "bidirectional"))
    )
    (net (code "46") (name "/SDIO_DAT3") (class "Default")
      (node (ref "MICROSD") (pin "DAT3") (pinfunction "DAT3_DAT3") (pintype "bidirectional"))
      (node (ref "R7") (pin "1") (pinfunction "1_1") (pintype "passive"))
      (node (ref "STM32F401") (pin "52") (pinfunction "PC11_52") (pintype "bidirectional"))
    )
    (net (code "47") (name "/STATE") (class "Default")
      (node (ref "JP1") (pin "1") (pinfunction "1_1") (pintype "passive"))
      (node (ref "STM32F401") (pin "41") (pinfunction "PA8_41") (pintype "bidirectional"))
    )
    (net (code "48") (name "/SVC") (class "Default")
      (node (ref "JP1") (pin "19") (pinfunction "19_19") (pintype "passive"))
      (node (ref "R6") (pin "1") (pinfunction "1_1") (pintype "passive"))
      (node (ref "STM32F401") (pin "49") (pinfunction "PA14_49") (pintype "bidirectional"))
    )
    (net (code "49") (name "/SVD") (class "Default")
      (node (ref "JP1") (pin "17") (pinfunction "17_17") (pintype "passive"))
      (node (ref "R5") (pin "1") (pinfunction "1_1") (pintype "passive"))
      (node (ref "STM32F401") (pin "46") (pinfunction "PA13_46") (pintype "bidirectional"))
    )
    (net (code "50") (name "/TCXO") (class "Default")
      (node (ref "C8") (pin "1") (pinfunction "1_1") (pintype "passive"))
      (node (ref "STM32F401") (pin "5") (pinfunction "PH0-OSC_IN_5") (pintype "bidirectional"))
    )
    (net (code "51") (name "/USIL_ON") (class "Default")
      (node (ref "JP6") (pin "6") (pinfunction "6_6") (pintype "passive"))
      (node (ref "STM32F401") (pin "62") (pinfunction "PB9_62") (pintype "bidirectional"))
    )
    (net (code "52") (name "/V_BAT") (class "Default")
      (node (ref "DC-DC_3V3") (pin "P$1") (pinfunction "IN+_P$1") (pintype "bidirectional"))
      (node (ref "DC-DC_3V3") (pin "P$2") (pinfunction "IN+_P$2") (pintype "bidirectional"))
      (node (ref "DC-DC_5V") (pin "P$1") (pinfunction "IN+_P$1") (pintype "bidirectional"))
      (node (ref "DC-DC_5V") (pin "P$2") (pinfunction "IN+_P$2") (pintype "bidirectional"))
      (node (ref "JP1") (pin "11") (pinfunction "11_11") (pintype "passive"))
    )
    (net (code "53") (name "Net-(3V3-Pad2)") (class "Default")
      (node (ref "3V3") (pin "2") (pinfunction "2_2") (pintype "passive"))
      (node (ref "5V") (pin "1") (pinfunction "1_1") (pintype "passive"))
      (node (ref "R17") (pin "1") (pinfunction "1_1") (pintype "passive"))
    )
    (net (code "54") (name "Net-(BUZZER-GND)") (class "Default")
      (node (ref "BUZZER") (pin "P$1") (pinfunction "GND_P$1") (pintype "bidirectional"))
      (node (ref "SI2301") (pin "3") (pinfunction "D_3") (pintype "bidirectional"))
    )
    (net (code "55") (name "Net-(PC13-PadC)") (class "Default")
      (node (ref "PC13") (pin "C") (pinfunction "C_C") (pintype "passive"))
      (node (ref "R4") (pin "2") (pinfunction "2_2") (pintype "passive"))
    )
    (net (code "56") (name "Net-(PWR-PadC)") (class "Default")
      (node (ref "PWR") (pin "C") (pinfunction "C_C") (pintype "passive"))
      (node (ref "R3") (pin "2") (pinfunction "2_2") (pintype "passive"))
    )
    (net (code "57") (name "Net-(Q24-OUTPUT)") (class "Default")
      (node (ref "C8") (pin "2") (pinfunction "2_2") (pintype "passive"))
      (node (ref "Q24") (pin "P$3") (pinfunction "OUTPUT_P$3") (pintype "bidirectional"))
    )
    (net (code "58") (name "Net-(SI2301-G)") (class "Default")
      (node (ref "R30") (pin "2") (pinfunction "2_2") (pintype "passive"))
      (node (ref "R31") (pin "1") (pinfunction "1_1") (pintype "passive"))
      (node (ref "SI2301") (pin "1") (pinfunction "G_1") (pintype "bidirectional"))
    )
    (net (code "59") (name "Net-(SI2301.2-G)") (class "Default")
      (node (ref "R24") (pin "2") (pinfunction "2_2") (pintype "passive"))
      (node (ref "R28") (pin "2") (pinfunction "2_2") (pintype "passive"))
      (node (ref "SI2301.2") (pin "1") (pinfunction "G_1") (pintype "bidirectional"))
    )
    (net (code "60") (name "Net-(SI2301.3-G)") (class "Default")
      (node (ref "R27") (pin "2") (pinfunction "2_2") (pintype "passive"))
      (node (ref "R29") (pin "1") (pinfunction "1_1") (pintype "passive"))
      (node (ref "SI2301.3") (pin "1") (pinfunction "G_1") (pintype "bidirectional"))
    )
    (net (code "61") (name "Net-(SI2301.4-G)") (class "Default")
      (node (ref "R18") (pin "2") (pinfunction "2_2") (pintype "passive"))
      (node (ref "R22") (pin "2") (pinfunction "2_2") (pintype "passive"))
      (node (ref "SI2301.4") (pin "1") (pinfunction "G_1") (pintype "bidirectional"))
    )
    (net (code "62") (name "Net-(SI2301.5-G)") (class "Default")
      (node (ref "R21") (pin "2") (pinfunction "2_2") (pintype "passive"))
      (node (ref "R23") (pin "1") (pinfunction "1_1") (pintype "passive"))
      (node (ref "SI2301.5") (pin "1") (pinfunction "G_1") (pintype "bidirectional"))
    )
    (net (code "63") (name "Net-(SI2301.6-G)") (class "Default")
      (node (ref "R33") (pin "2") (pinfunction "2_2") (pintype "passive"))
      (node (ref "R34") (pin "2") (pinfunction "2_2") (pintype "passive"))
      (node (ref "SI2301.6") (pin "1") (pinfunction "G_1") (pintype "bidirectional"))
    )
    (net (code "64") (name "Net-(SI2301.7-G)") (class "Default")
      (node (ref "R11") (pin "2") (pinfunction "2_2") (pintype "passive"))
      (node (ref "R15") (pin "2") (pinfunction "2_2") (pintype "passive"))
      (node (ref "SI2301.7") (pin "1") (pinfunction "G_1") (pintype "bidirectional"))
    )
    (net (code "65") (name "Net-(SI2301.8-G)") (class "Default")
      (node (ref "R14") (pin "2") (pinfunction "2_2") (pintype "passive"))
      (node (ref "R16") (pin "1") (pinfunction "1_1") (pintype "passive"))
      (node (ref "SI2301.8") (pin "1") (pinfunction "G_1") (pintype "bidirectional"))
    )
    (net (code "66") (name "Net-(STM32F401-VCAP_1)") (class "Default")
      (node (ref "C11") (pin "1") (pinfunction "1_1") (pintype "passive"))
      (node (ref "STM32F401") (pin "30") (pinfunction "VCAP_1_30") (pintype "bidirectional"))
    )
    (net (code "67") (name "Net-(U$12-P1N1D)") (class "Default")
      (node (ref "JP3") (pin "1") (pinfunction "1_1") (pintype "passive"))
      (node (ref "JP4") (pin "1") (pinfunction "1_1") (pintype "passive"))
      (node (ref "U$12") (pin "2") (pinfunction "P1N1D_2") (pintype "passive"))
    )
    (net (code "68") (name "Net-(U$12-P2N2D)") (class "Default")
      (node (ref "JP3") (pin "2") (pinfunction "2_2") (pintype "passive"))
      (node (ref "JP4") (pin "2") (pinfunction "2_2") (pintype "passive"))
      (node (ref "U$12") (pin "6") (pinfunction "P2N2D_6") (pintype "passive"))
    )
    (net (code "69") (name "Net-(U$16-P1N1D)") (class "Default")
      (node (ref "JP2") (pin "1") (pinfunction "1_1") (pintype "passive"))
      (node (ref "U$16") (pin "2") (pinfunction "P1N1D_2") (pintype "passive"))
    )
    (net (code "70") (name "Net-(U$16-P2N2D)") (class "Default")
      (node (ref "JP2") (pin "2") (pinfunction "2_2") (pintype "passive"))
      (node (ref "U$16") (pin "6") (pinfunction "P2N2D_6") (pintype "passive"))
    )
    (net (code "71") (name "unconnected-(JP1-Pad2)") (class "Default")
      (node (ref "JP1") (pin "2") (pinfunction "2_2") (pintype "passive"))
    )
    (net (code "72") (name "unconnected-(LIS3MDL-DRDY-PadP$8)") (class "Default")
      (node (ref "LIS3MDL") (pin "P$8") (pinfunction "DRDY_P$8") (pintype "bidirectional"))
    )
    (net (code "73") (name "unconnected-(LIS3MDL-INT-PadP$7)") (class "Default")
      (node (ref "LIS3MDL") (pin "P$7") (pinfunction "INT_P$7") (pintype "bidirectional"))
    )
    (net (code "74") (name "unconnected-(LSM6DS3-VIN-PadP$7)") (class "Default")
      (node (ref "LSM6DS3") (pin "P$7") (pinfunction "VIN_P$7") (pintype "bidirectional"))
    )
    (net (code "75") (name "unconnected-(Q24-STANDBY-PadP$1)") (class "Default")
      (node (ref "Q24") (pin "P$1") (pinfunction "STANDBY_P$1") (pintype "bidirectional"))
    )
    (net (code "76") (name "unconnected-(STM32F401-BOOT0-Pad60)") (class "Default")
      (node (ref "STM32F401") (pin "60") (pinfunction "BOOT0_60") (pintype "bidirectional"))
    )
    (net (code "77") (name "unconnected-(STM32F401-PA0-Pad14)") (class "Default")
      (node (ref "STM32F401") (pin "14") (pinfunction "PA0_14") (pintype "bidirectional"))
    )
    (net (code "78") (name "unconnected-(STM32F401-PA1-Pad15)") (class "Default")
      (node (ref "STM32F401") (pin "15") (pinfunction "PA1_15") (pintype "bidirectional"))
    )
    (net (code "79") (name "unconnected-(STM32F401-PA2-Pad16)") (class "Default")
      (node (ref "STM32F401") (pin "16") (pinfunction "PA2_16") (pintype "bidirectional"))
    )
    (net (code "80") (name "unconnected-(STM32F401-PA3-Pad17)") (class "Default")
      (node (ref "STM32F401") (pin "17") (pinfunction "PA3_17") (pintype "bidirectional"))
    )
    (net (code "81") (name "unconnected-(STM32F401-PA4-Pad20)") (class "Default")
      (node (ref "STM32F401") (pin "20") (pinfunction "PA4_20") (pintype "bidirectional"))
    )
    (net (code "82") (name "unconnected-(STM32F401-PA5-Pad21)") (class "Default")
      (node (ref "STM32F401") (pin "21") (pinfunction "PA5_21") (pintype "bidirectional"))
    )
    (net (code "83") (name "unconnected-(STM32F401-PB5-Pad57)") (class "Default")
      (node (ref "STM32F401") (pin "57") (pinfunction "PB5_57") (pintype "bidirectional"))
    )
    (net (code "84") (name "unconnected-(STM32F401-PB8-Pad61)") (class "Default")
      (node (ref "STM32F401") (pin "61") (pinfunction "PB8_61") (pintype "bidirectional"))
    )
    (net (code "85") (name "unconnected-(STM32F401-PC2-Pad10)") (class "Default")
      (node (ref "STM32F401") (pin "10") (pinfunction "PC2_10") (pintype "bidirectional"))
    )
    (net (code "86") (name "unconnected-(STM32F401-PC14-_OSC32_IN-Pad3)") (class "Default")
      (node (ref "STM32F401") (pin "3") (pinfunction "PC14-_OSC32_IN_3") (pintype "bidirectional"))
    )
    (net (code "87") (name "unconnected-(STM32F401-PC15-_OSC32_OUT-Pad4)") (class "Default")
      (node (ref "STM32F401") (pin "4") (pinfunction "PC15-_OSC32_OUT_4") (pintype "bidirectional"))
    )
    (net (code "88") (name "unconnected-(STM32F401-PH1-_OSC_OUT-Pad6)") (class "Default")
      (node (ref "STM32F401") (pin "6") (pinfunction "PH1-_OSC_OUT_6") (pintype "bidirectional"))
    )
    (net (code "89") (name "unconnected-(STM32F401-VBAT-Pad1)") (class "Default")
      (node (ref "STM32F401") (pin "1") (pinfunction "VBAT_1") (pintype "bidirectional"))
    )
  )
)
